# btpro.net
KiCad netlist of a schematic drawn in EAGLE
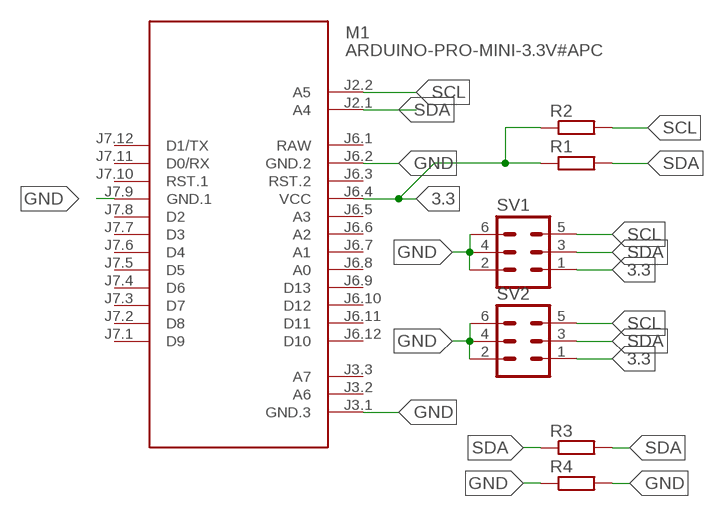
[diagram p0: schematic, sheet 1]

(export (version "E")
  (design (tool "Eeschema 10.0.6"))
  (components
    (comp (ref "M1")
      (value "ARDUINO-PRO-MINI-3.3V#APC")
      (footprint "eagle-import:ARDUINO-PRO-MINI#APC")
      (libsource (lib "eagle-import") (part "ARDUINO-PRO-MINI-#APC3.3V"))
    )
    (comp (ref "R1")
      (value "R-EU_0411/12")
      (footprint "eagle-import:0411_12")
      (libsource (lib "eagle-import") (part "R-EU_0411/12"))
    )
    (comp (ref "R2")
      (value "R-EU_0411/12")
      (footprint "eagle-import:0411_12")
      (libsource (lib "eagle-import") (part "R-EU_0411/12"))
    )
    (comp (ref "R3")
      (value "R-EU_0207/10")
      (footprint "eagle-import:0207_10")
      (libsource (lib "eagle-import") (part "R-EU_0207/10"))
    )
    (comp (ref "R4")
      (value "R-EU_0207/10")
      (footprint "eagle-import:0207_10")
      (libsource (lib "eagle-import") (part "R-EU_0207/10"))
    )
    (comp (ref "SV1")
      (value "ML6")
      (footprint "eagle-import:ML6")
      (libsource (lib "eagle-import") (part "ML6"))
    )
    (comp (ref "SV2")
      (value "ML6")
      (footprint "eagle-import:ML6")
      (libsource (lib "eagle-import") (part "ML6"))
    )
  )
  (nets
    (net (code "1") (name "/RAW") (class "Default")
      (node (ref "M1") (pin "J6.1") (pinfunction "RAW_J6.1") (pintype "power_in"))
    )
    (net (code "2") (name "3.3") (class "Default")
      (node (ref "M1") (pin "J6.4") (pinfunction "VCC_J6.4") (pintype "power_in"))
      (node (ref "R1") (pin "1") (pinfunction "1_1") (pintype "passive"))
      (node (ref "R2") (pin "1") (pinfunction "1_1") (pintype "passive"))
      (node (ref "SV1") (pin "1") (pinfunction "1_1") (pintype "passive"))
      (node (ref "SV2") (pin "1") (pinfunction "1_1") (pintype "passive"))
    )
    (net (code "3") (name "GND") (class "Default")
      (node (ref "M1") (pin "J3.1") (pinfunction "GND.3_J3.1") (pintype "bidirectional"))
      (node (ref "M1") (pin "J6.2") (pinfunction "GND.2_J6.2") (pintype "power_in"))
      (node (ref "M1") (pin "J7.9") (pinfunction "GND.1_J7.9") (pintype "power_in"))
      (node (ref "R4") (pin "1") (pinfunction "1_1") (pintype "passive"))
      (node (ref "R4") (pin "2") (pinfunction "2_2") (pintype "passive"))
      (node (ref "SV1") (pin "2") (pinfunction "2_2") (pintype "passive"))
      (node (ref "SV1") (pin "4") (pinfunction "4_4") (pintype "passive"))
      (node (ref "SV1") (pin "6") (pinfunction "6_6") (pintype "passive"))
      (node (ref "SV2") (pin "2") (pinfunction "2_2") (pintype "passive"))
      (node (ref "SV2") (pin "4") (pinfunction "4_4") (pintype "passive"))
      (node (ref "SV2") (pin "6") (pinfunction "6_6") (pintype "passive"))
    )
    (net (code "4") (name "SCL") (class "Default")
      (node (ref "M1") (pin "J2.2") (pinfunction "A5_J2.2") (pintype "bidirectional"))
      (node (ref "R2") (pin "2") (pinfunction "2_2") (pintype "passive"))
      (node (ref "SV1") (pin "5") (pinfunction "5_5") (pintype "passive"))
      (node (ref "SV2") (pin "5") (pinfunction "5_5") (pintype "passive"))
    )
    (net (code "5") (name "SDA") (class "Default")
      (node (ref "M1") (pin "J2.1") (pinfunction "A4_J2.1") (pintype "bidirectional"))
      (node (ref "R1") (pin "2") (pinfunction "2_2") (pintype "passive"))
      (node (ref "R3") (pin "1") (pinfunction "1_1") (pintype "passive"))
      (node (ref "R3") (pin "2") (pinfunction "2_2") (pintype "passive"))
      (node (ref "SV1") (pin "3") (pinfunction "3_3") (pintype "passive"))
      (node (ref "SV2") (pin "3") (pinfunction "3_3") (pintype "passive"))
    )
    (net (code "6") (name "unconnected-(M1-A0-PadJ6.8)") (class "Default")
      (node (ref "M1") (pin "J6.8") (pinfunction "A0_J6.8") (pintype "bidirectional"))
    )
    (net (code "7") (name "unconnected-(M1-A1-PadJ6.7)") (class "Default")
      (node (ref "M1") (pin "J6.7") (pinfunction "A1_J6.7") (pintype "bidirectional"))
    )
    (net (code "8") (name "unconnected-(M1-A2-PadJ6.6)") (class "Default")
      (node (ref "M1") (pin "J6.6") (pinfunction "A2_J6.6") (pintype "bidirectional"))
    )
    (net (code "9") (name "unconnected-(M1-A3-PadJ6.5)") (class "Default")
      (node (ref "M1") (pin "J6.5") (pinfunction "A3_J6.5") (pintype "bidirectional"))
    )
    (net (code "10") (name "unconnected-(M1-A6-PadJ3.2)") (class "Default")
      (node (ref "M1") (pin "J3.2") (pinfunction "A6_J3.2") (pintype "bidirectional"))
    )
    (net (code "11") (name "unconnected-(M1-A7-PadJ3.3)") (class "Default")
      (node (ref "M1") (pin "J3.3") (pinfunction "A7_J3.3") (pintype "bidirectional"))
    )
    (net (code "12") (name "unconnected-(M1-D0{slash}RX-PadJ7.11)") (class "Default")
      (node (ref "M1") (pin "J7.11") (pinfunction "D0/RX_J7.11") (pintype "bidirectional"))
    )
    (net (code "13") (name "unconnected-(M1-D1{slash}TX-PadJ7.12)") (class "Default")
      (node (ref "M1") (pin "J7.12") (pinfunction "D1/TX_J7.12") (pintype "bidirectional"))
    )
    (net (code "14") (name "unconnected-(M1-D2-PadJ7.8)") (class "Default")
      (node (ref "M1") (pin "J7.8") (pinfunction "D2_J7.8") (pintype "bidirectional"))
    )
    (net (code "15") (name "unconnected-(M1-D3-PadJ7.7)") (class "Default")
      (node (ref "M1") (pin "J7.7") (pinfunction "D3_J7.7") (pintype "bidirectional"))
    )
    (net (code "16") (name "unconnected-(M1-D4-PadJ7.6)") (class "Default")
      (node (ref "M1") (pin "J7.6") (pinfunction "D4_J7.6") (pintype "bidirectional"))
    )
    (net (code "17") (name "unconnected-(M1-D5-PadJ7.5)") (class "Default")
      (node (ref "M1") (pin "J7.5") (pinfunction "D5_J7.5") (pintype "bidirectional"))
    )
    (net (code "18") (name "unconnected-(M1-D6-PadJ7.4)") (class "Default")
      (node (ref "M1") (pin "J7.4") (pinfunction "D6_J7.4") (pintype "bidirectional"))
    )
    (net (code "19") (name "unconnected-(M1-D7-PadJ7.3)") (class "Default")
      (node (ref "M1") (pin "J7.3") (pinfunction "D7_J7.3") (pintype "bidirectional"))
    )
    (net (code "20") (name "unconnected-(M1-D8-PadJ7.2)") (class "Default")
      (node (ref "M1") (pin "J7.2") (pinfunction "D8_J7.2") (pintype "bidirectional"))
    )
    (net (code "21") (name "unconnected-(M1-D9-PadJ7.1)") (class "Default")
      (node (ref "M1") (pin "J7.1") (pinfunction "D9_J7.1") (pintype "bidirectional"))
    )
    (net (code "22") (name "unconnected-(M1-D10-PadJ6.12)") (class "Default")
      (node (ref "M1") (pin "J6.12") (pinfunction "D10_J6.12") (pintype "bidirectional"))
    )
    (net (code "23") (name "unconnected-(M1-D11-PadJ6.11)") (class "Default")
      (node (ref "M1") (pin "J6.11") (pinfunction "D11_J6.11") (pintype "bidirectional"))
    )
    (net (code "24") (name "unconnected-(M1-D12-PadJ6.10)") (class "Default")
      (node (ref "M1") (pin "J6.10") (pinfunction "D12_J6.10") (pintype "bidirectional"))
    )
    (net (code "25") (name "unconnected-(M1-D13-PadJ6.9)") (class "Default")
      (node (ref "M1") (pin "J6.9") (pinfunction "D13_J6.9") (pintype "bidirectional"))
    )
    (net (code "26") (name "unconnected-(M1-RST.1-PadJ7.10)") (class "Default")
      (node (ref "M1") (pin "J7.10") (pinfunction "RST.1_J7.10") (pintype "bidirectional"))
    )
    (net (code "27") (name "unconnected-(M1-RST.2-PadJ6.3)") (class "Default")
      (node (ref "M1") (pin "J6.3") (pinfunction "RST.2_J6.3") (pintype "bidirectional"))
    )
  )
)
